# Apo_Board_2017_Capsense.net
KiCad netlist of a schematic drawn in EAGLE
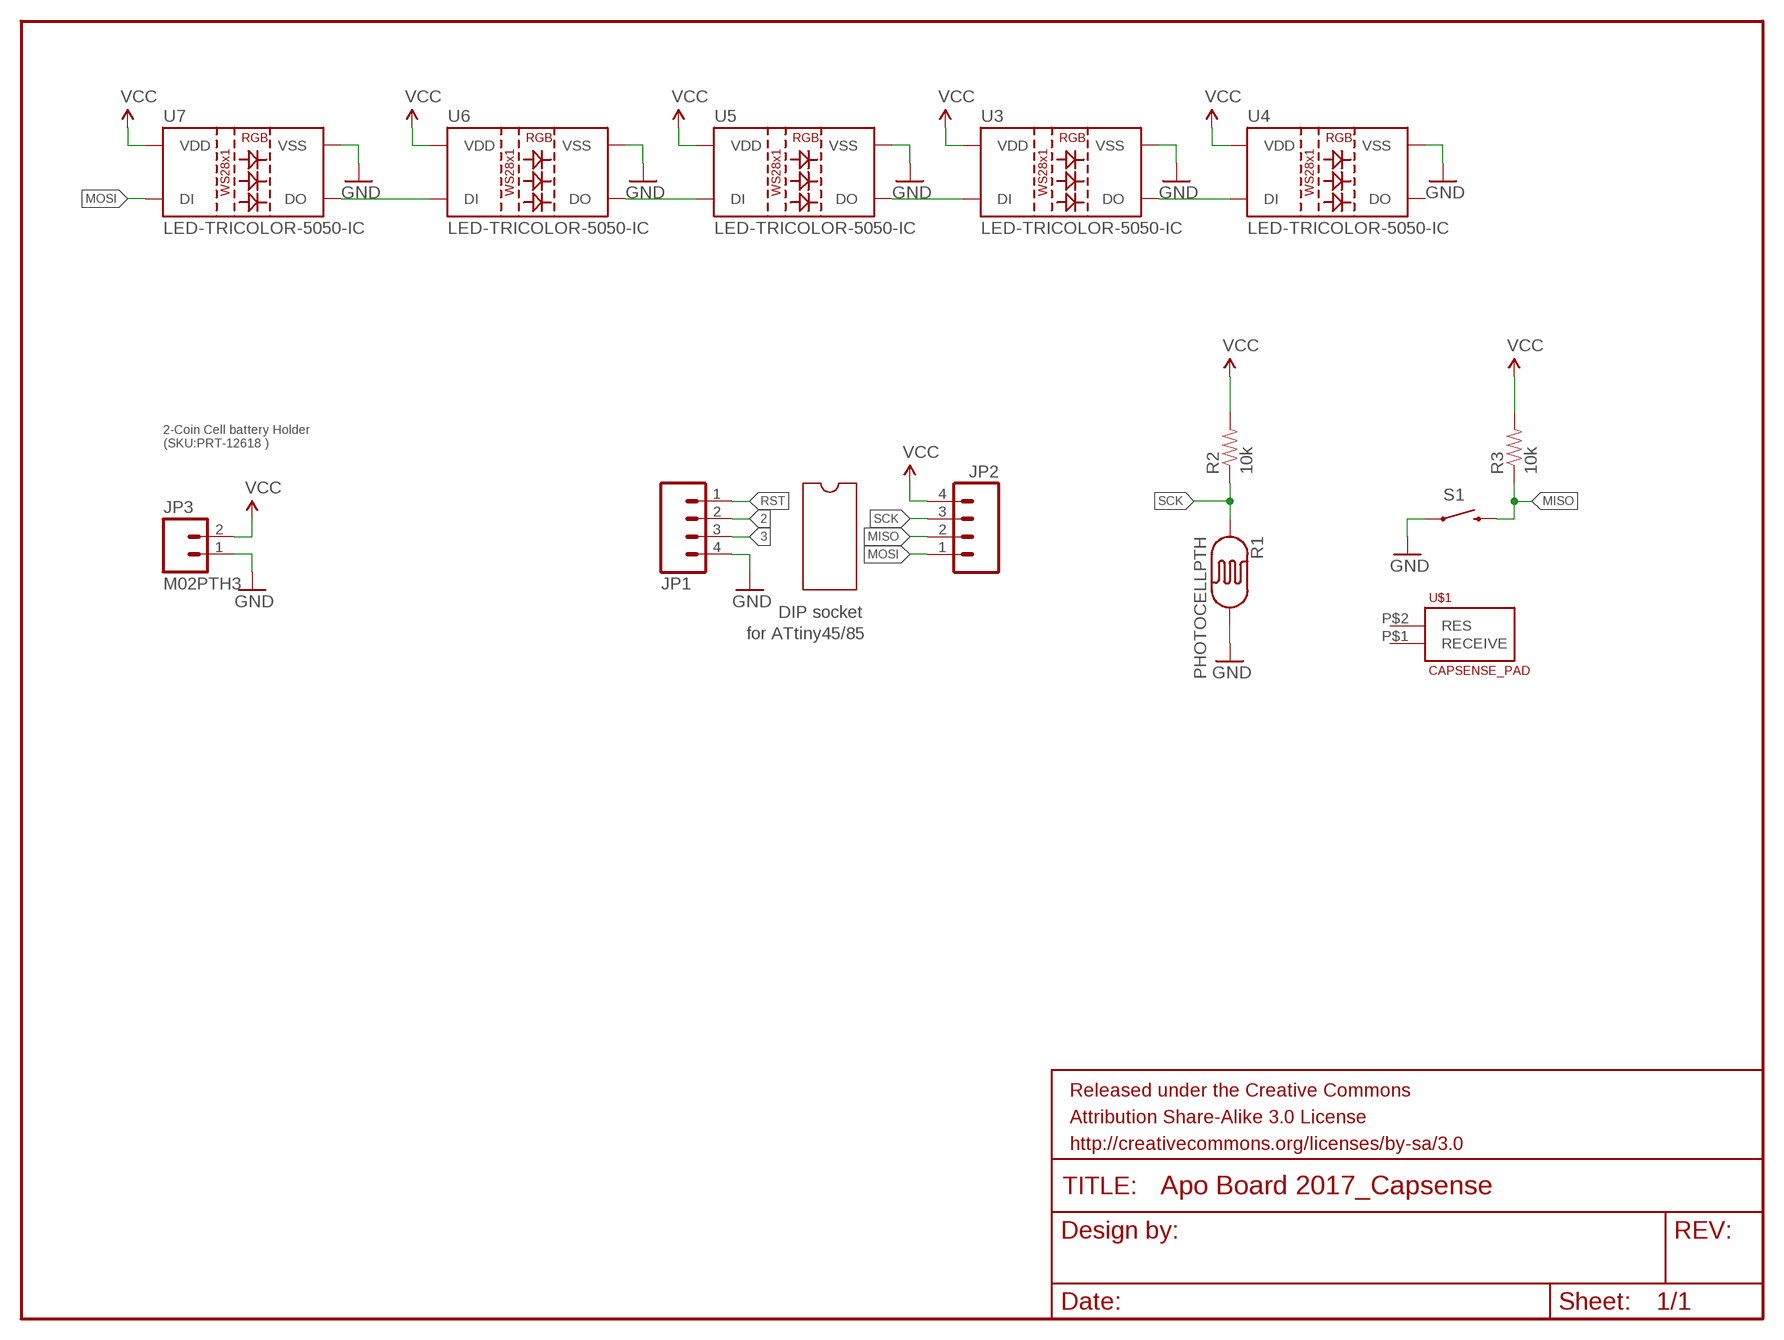
[diagram p0: schematic, sheet 1]

(export (version "E")
  (design (tool "Eeschema 10.0.6"))
  (components
    (comp (ref "FRAME1")
      (value "FRAME-LETTER")
      (footprint "eagle-import:CREATIVE_COMMONS")
      (libsource (lib "eagle-import") (part "FRAME-LETTER"))
    )
    (comp (ref "JP1")
      (value "M04PTH")
      (footprint "eagle-import:1X04")
      (libsource (lib "eagle-import") (part "M04PTH"))
    )
    (comp (ref "JP2")
      (value "M04PTH")
      (footprint "eagle-import:1X04")
      (libsource (lib "eagle-import") (part "M04PTH"))
    )
    (comp (ref "JP3")
      (value "M02PTH3")
      (footprint "eagle-import:1X02_LONGPADS")
      (libsource (lib "eagle-import") (part "M02PTH3"))
    )
    (comp (ref "R1")
      (value "PHOTOCELLPTH")
      (footprint "eagle-import:PHOTOCELL")
      (libsource (lib "eagle-import") (part "PHOTOCELLPTH"))
    )
    (comp (ref "R2")
      (value "10k")
      (footprint "eagle-import:AXIAL-0.4")
      (libsource (lib "eagle-import") (part "RESISTORPTH-1/4W"))
    )
    (comp (ref "R3")
      (value "10k")
      (footprint "eagle-import:AXIAL-0.4")
      (libsource (lib "eagle-import") (part "RESISTORPTH-1/4W"))
    )
    (comp (ref "S1")
      (value "SWITCH-MOMENTARY-2PTH")
      (footprint "eagle-import:TACTILE-PTH")
      (libsource (lib "eagle-import") (part "SWITCH-MOMENTARY-2PTH"))
    )
    (comp (ref "U$1")
      (value "CAPSENSE_PAD")
      (footprint "eagle-import:CAPSENSE_PAD")
      (libsource (lib "eagle-import") (part "CAPSENSE_PAD"))
    )
    (comp (ref "U3")
      (value "LED-TRICOLOR-5050-IC")
      (footprint "eagle-import:LED-RGB-THRU")
      (libsource (lib "eagle-import") (part "LED-TRICOLOR-5050-IC"))
    )
    (comp (ref "U4")
      (value "LED-TRICOLOR-5050-IC")
      (footprint "eagle-import:LED-RGB-THRU")
      (libsource (lib "eagle-import") (part "LED-TRICOLOR-5050-IC"))
    )
    (comp (ref "U5")
      (value "LED-TRICOLOR-5050-IC")
      (footprint "eagle-import:LED-RGB-THRU")
      (libsource (lib "eagle-import") (part "LED-TRICOLOR-5050-IC"))
    )
    (comp (ref "U6")
      (value "LED-TRICOLOR-5050-IC")
      (footprint "eagle-import:LED-RGB-THRU")
      (libsource (lib "eagle-import") (part "LED-TRICOLOR-5050-IC"))
    )
    (comp (ref "U7")
      (value "LED-TRICOLOR-5050-IC")
      (footprint "eagle-import:LED-RGB-THRU")
      (libsource (lib "eagle-import") (part "LED-TRICOLOR-5050-IC"))
    )
  )
  (nets
    (net (code "1") (name "2") (class "Default")
      (node (ref "JP1") (pin "2") (pinfunction "2_2") (pintype "passive"))
    )
    (net (code "2") (name "3") (class "Default")
      (node (ref "JP1") (pin "3") (pinfunction "3_3") (pintype "passive"))
    )
    (net (code "3") (name "GND") (class "Default")
      (node (ref "JP1") (pin "4") (pinfunction "4_4") (pintype "passive"))
      (node (ref "JP3") (pin "1") (pinfunction "1_1") (pintype "passive"))
      (node (ref "R1") (pin "2") (pinfunction "P$2_2") (pintype "bidirectional"))
      (node (ref "S1") (pin "1") (pinfunction "1_1") (pintype "passive"))
      (node (ref "U3") (pin "3") (pinfunction "VSS_3") (pintype "bidirectional"))
      (node (ref "U4") (pin "3") (pinfunction "VSS_3") (pintype "bidirectional"))
      (node (ref "U5") (pin "3") (pinfunction "VSS_3") (pintype "bidirectional"))
      (node (ref "U6") (pin "3") (pinfunction "VSS_3") (pintype "bidirectional"))
      (node (ref "U7") (pin "3") (pinfunction "VSS_3") (pintype "bidirectional"))
    )
    (net (code "4") (name "MISO") (class "Default")
      (node (ref "JP2") (pin "2") (pinfunction "2_2") (pintype "passive"))
      (node (ref "R3") (pin "P$1") (pinfunction "1_P$1") (pintype "passive"))
      (node (ref "S1") (pin "3") (pinfunction "2_3") (pintype "passive"))
    )
    (net (code "5") (name "MOSI") (class "Default")
      (node (ref "JP2") (pin "1") (pinfunction "1_1") (pintype "passive"))
      (node (ref "U7") (pin "1") (pinfunction "DI_1") (pintype "bidirectional"))
    )
    (net (code "6") (name "Net-(U3-DI)") (class "Default")
      (node (ref "U3") (pin "1") (pinfunction "DI_1") (pintype "bidirectional"))
      (node (ref "U5") (pin "4") (pinfunction "DO_4") (pintype "bidirectional"))
    )
    (net (code "7") (name "Net-(U3-DO)") (class "Default")
      (node (ref "U3") (pin "4") (pinfunction "DO_4") (pintype "bidirectional"))
      (node (ref "U4") (pin "1") (pinfunction "DI_1") (pintype "bidirectional"))
    )
    (net (code "8") (name "Net-(U5-DI)") (class "Default")
      (node (ref "U5") (pin "1") (pinfunction "DI_1") (pintype "bidirectional"))
      (node (ref "U6") (pin "4") (pinfunction "DO_4") (pintype "bidirectional"))
    )
    (net (code "9") (name "Net-(U6-DI)") (class "Default")
      (node (ref "U6") (pin "1") (pinfunction "DI_1") (pintype "bidirectional"))
      (node (ref "U7") (pin "4") (pinfunction "DO_4") (pintype "bidirectional"))
    )
    (net (code "10") (name "RST") (class "Default")
      (node (ref "JP1") (pin "1") (pinfunction "1_1") (pintype "passive"))
    )
    (net (code "11") (name "SCK") (class "Default")
      (node (ref "JP2") (pin "3") (pinfunction "3_3") (pintype "passive"))
      (node (ref "R1") (pin "1") (pinfunction "P$1_1") (pintype "bidirectional"))
      (node (ref "R2") (pin "P$1") (pinfunction "1_P$1") (pintype "passive"))
    )
    (net (code "12") (name "VCC") (class "Default")
      (node (ref "JP2") (pin "4") (pinfunction "4_4") (pintype "passive"))
      (node (ref "JP3") (pin "2") (pinfunction "2_2") (pintype "passive"))
      (node (ref "R2") (pin "P$2") (pinfunction "2_P$2") (pintype "passive"))
      (node (ref "R3") (pin "P$2") (pinfunction "2_P$2") (pintype "passive"))
      (node (ref "U3") (pin "2") (pinfunction "VDD_2") (pintype "bidirectional"))
      (node (ref "U4") (pin "2") (pinfunction "VDD_2") (pintype "bidirectional"))
      (node (ref "U5") (pin "2") (pinfunction "VDD_2") (pintype "bidirectional"))
      (node (ref "U6") (pin "2") (pinfunction "VDD_2") (pintype "bidirectional"))
      (node (ref "U7") (pin "2") (pinfunction "VDD_2") (pintype "bidirectional"))
    )
    (net (code "13") (name "unconnected-(U$1-RECEIVE-PadP$1)") (class "Default")
      (node (ref "U$1") (pin "P$1") (pinfunction "RECEIVE_P$1") (pintype "bidirectional"))
    )
    (net (code "14") (name "unconnected-(U$1-RES-PadP$2)") (class "Default")
      (node (ref "U$1") (pin "P$2") (pinfunction "RES_P$2") (pintype "bidirectional"))
    )
    (net (code "15") (name "unconnected-(U4-DO-Pad4)") (class "Default")
      (node (ref "U4") (pin "4") (pinfunction "DO_4") (pintype "bidirectional"))
    )
  )
)
